# untitled.net
KiCad netlist of a schematic drawn in EAGLE
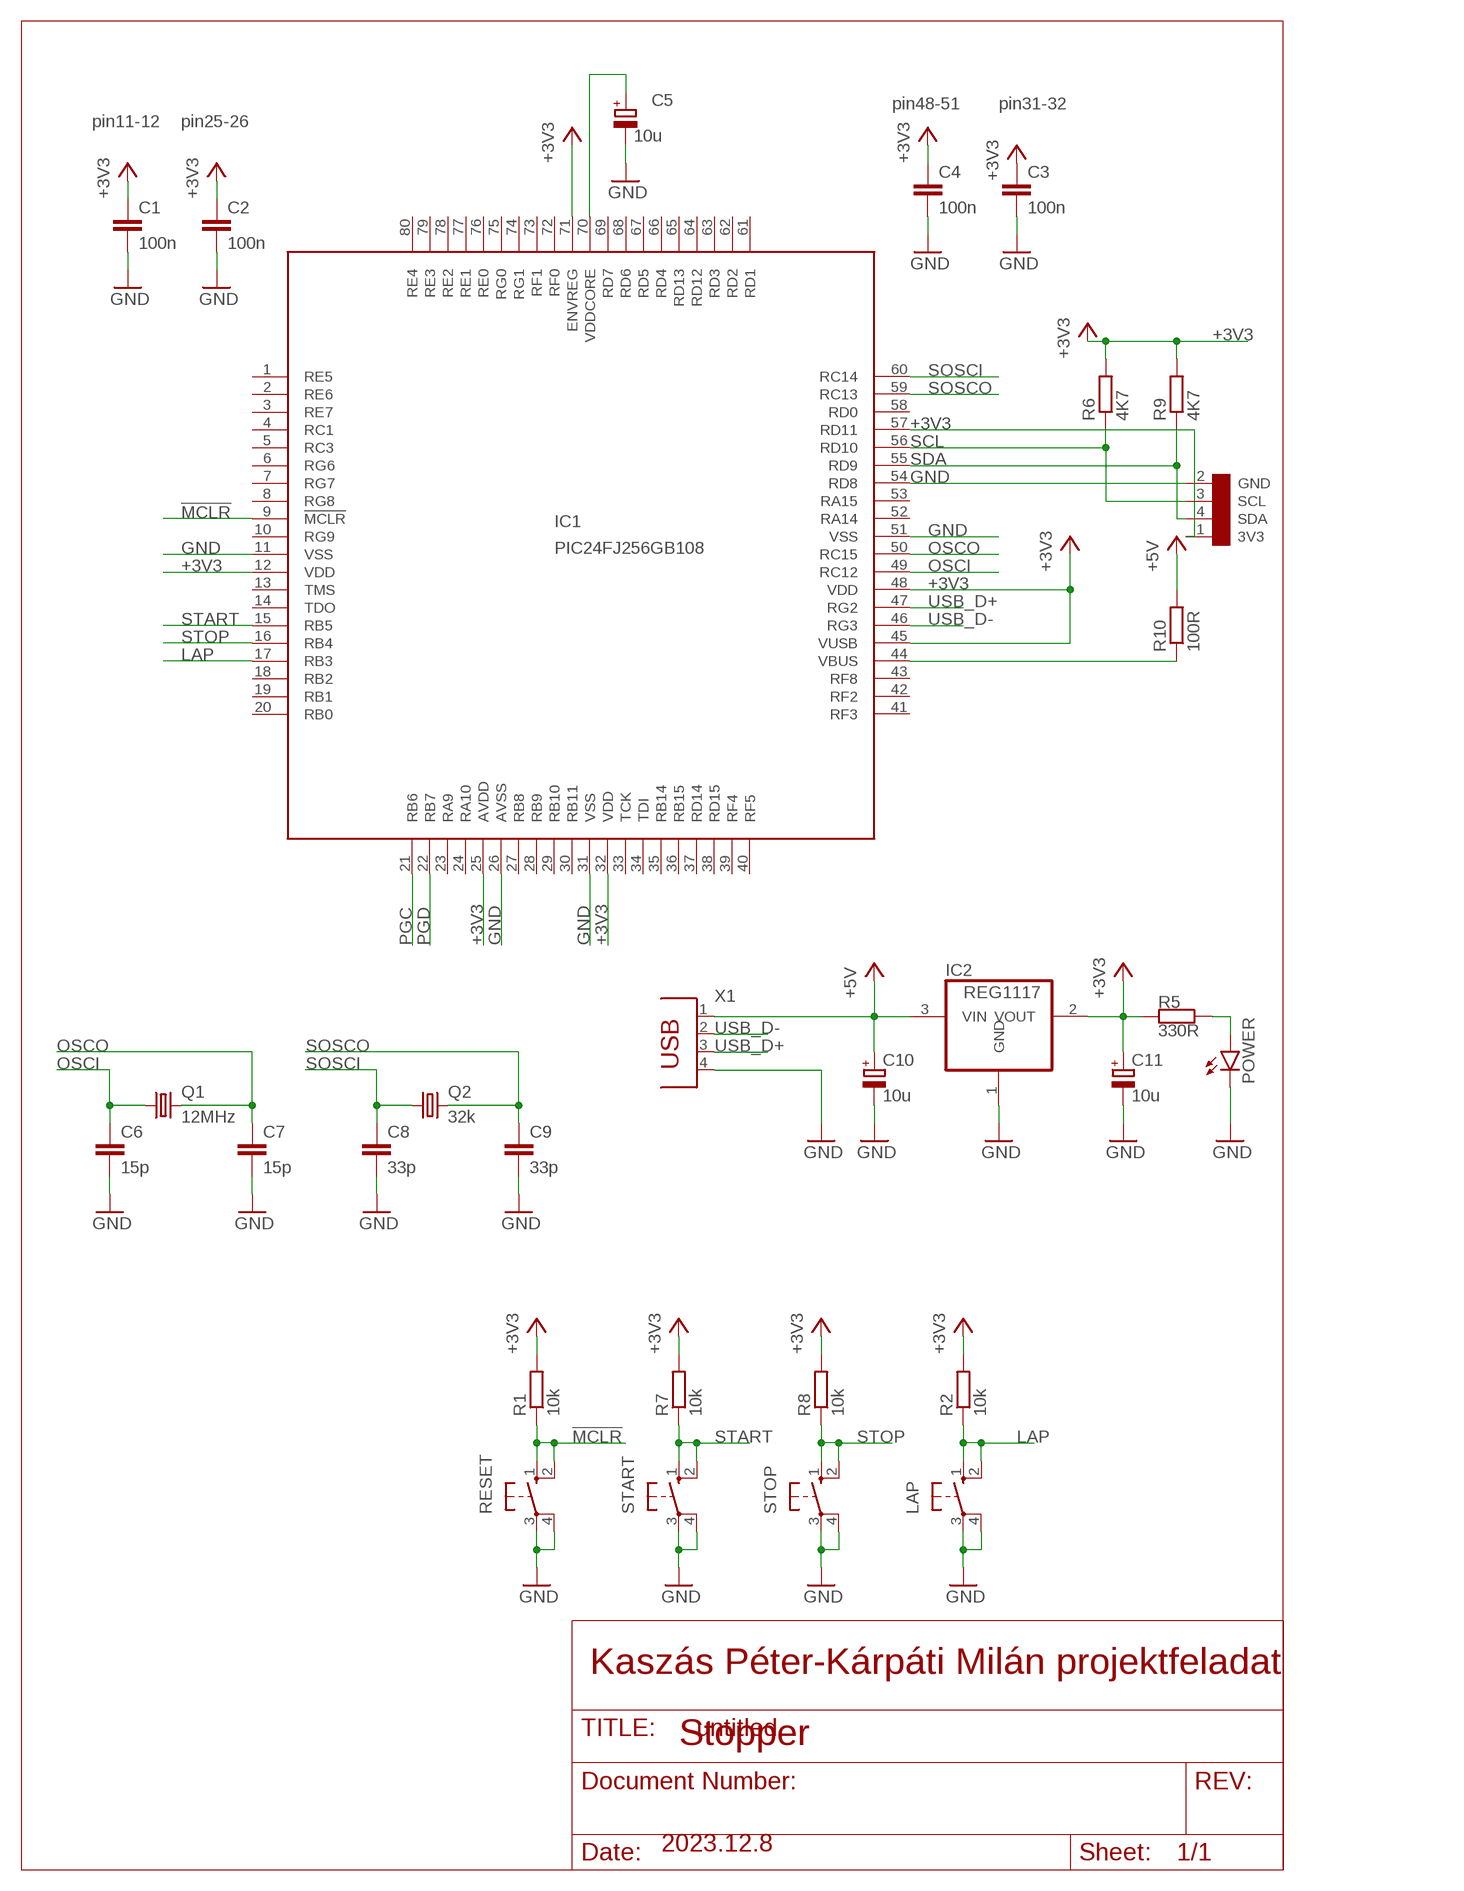
[diagram p0: schematic, sheet 1]

(export (version "E")
  (design (tool "Eeschema 10.0.6"))
  (components
    (comp (ref "C1")
      (value "100n")
      (footprint "eagle-import:C1206")
      (libsource (lib "eagle-import") (part "C-EUC1206"))
    )
    (comp (ref "C2")
      (value "100n")
      (footprint "eagle-import:C1206")
      (libsource (lib "eagle-import") (part "C-EUC1206"))
    )
    (comp (ref "C3")
      (value "100n")
      (footprint "eagle-import:C1206")
      (libsource (lib "eagle-import") (part "C-EUC1206"))
    )
    (comp (ref "C4")
      (value "100n")
      (footprint "eagle-import:C1206")
      (libsource (lib "eagle-import") (part "C-EUC1206"))
    )
    (comp (ref "C5")
      (value "10u")
      (footprint "eagle-import:SMC_D")
      (libsource (lib "eagle-import") (part "CPOL-EUSMCD"))
    )
    (comp (ref "C6")
      (value "15p")
      (footprint "eagle-import:C1206")
      (libsource (lib "eagle-import") (part "C-EUC1206"))
    )
    (comp (ref "C7")
      (value "15p")
      (footprint "eagle-import:C1206")
      (libsource (lib "eagle-import") (part "C-EUC1206"))
    )
    (comp (ref "C8")
      (value "33p")
      (footprint "eagle-import:C1206")
      (libsource (lib "eagle-import") (part "C-EUC1206"))
    )
    (comp (ref "C9")
      (value "33p")
      (footprint "eagle-import:C1206")
      (libsource (lib "eagle-import") (part "C-EUC1206"))
    )
    (comp (ref "C10")
      (value "10u")
      (footprint "eagle-import:SMC_D")
      (libsource (lib "eagle-import") (part "CPOL-EUSMCD"))
    )
    (comp (ref "C11")
      (value "10u")
      (footprint "eagle-import:SMC_D")
      (libsource (lib "eagle-import") (part "CPOL-EUSMCD"))
    )
    (comp (ref "CON1")
      (value "ICSPI2CTUSKE")
      (footprint "eagle-import:HDRV4W64P254_1X4_1016X508X838B")
      (libsource (lib "eagle-import") (part "ICSPI2CTUSKE"))
    )
    (comp (ref "IC1")
      (value "PIC24FJ256GB108")
      (footprint "eagle-import:TQFP80-12X12")
      (fields (field (name "MPN") "PIC24FJ256GB108-I/PT"))
      (libsource (lib "eagle-import") (part "PIC24FJ256GB108"))
    )
    (comp (ref "IC2")
      (value "REG1117")
      (footprint "eagle-import:SOT223")
      (libsource (lib "eagle-import") (part "REG1117"))
    )
    (comp (ref "LAP")
      (value "10-XX")
      (footprint "eagle-import:B3F-10XX")
      (fields (field (name "MPN") "B3F-1000"))
      (libsource (lib "eagle-import") (part "10-XX"))
    )
    (comp (ref "POWER")
      (value "LED5MM")
      (footprint "eagle-import:LED5MM")
      (libsource (lib "eagle-import") (part "LED5MM"))
    )
    (comp (ref "Q1")
      (value "12MHz")
      (footprint "eagle-import:HC49U70")
      (libsource (lib "eagle-import") (part "CRYSTALHC49U70"))
    )
    (comp (ref "Q2")
      (value "32k")
      (footprint "eagle-import:TC26H")
      (libsource (lib "eagle-import") (part "CRYSTALTC26H"))
    )
    (comp (ref "R1")
      (value "10k")
      (footprint "eagle-import:R1206")
      (libsource (lib "eagle-import") (part "R-EU_R1206"))
    )
    (comp (ref "R2")
      (value "10k")
      (footprint "eagle-import:R1206")
      (libsource (lib "eagle-import") (part "R-EU_R1206"))
    )
    (comp (ref "R5")
      (value "330R")
      (footprint "eagle-import:R1206")
      (libsource (lib "eagle-import") (part "R-EU_R1206"))
    )
    (comp (ref "R6")
      (value "4K7")
      (footprint "eagle-import:R1206")
      (libsource (lib "eagle-import") (part "R-EU_R1206"))
    )
    (comp (ref "R7")
      (value "10k")
      (footprint "eagle-import:R1206")
      (libsource (lib "eagle-import") (part "R-EU_R1206"))
    )
    (comp (ref "R8")
      (value "10k")
      (footprint "eagle-import:R1206")
      (libsource (lib "eagle-import") (part "R-EU_R1206"))
    )
    (comp (ref "R9")
      (value "4K7")
      (footprint "eagle-import:R1206")
      (libsource (lib "eagle-import") (part "R-EU_R1206"))
    )
    (comp (ref "R10")
      (value "100R")
      (footprint "eagle-import:R1206")
      (libsource (lib "eagle-import") (part "R-EU_R1206"))
    )
    (comp (ref "RESET")
      (value "10-XX")
      (footprint "eagle-import:B3F-10XX")
      (fields (field (name "MPN") "B3F-1000"))
      (libsource (lib "eagle-import") (part "10-XX"))
    )
    (comp (ref "START")
      (value "10-XX")
      (footprint "eagle-import:B3F-10XX")
      (fields (field (name "MPN") "B3F-1000"))
      (libsource (lib "eagle-import") (part "10-XX"))
    )
    (comp (ref "STOP")
      (value "10-XX")
      (footprint "eagle-import:B3F-10XX")
      (fields (field (name "MPN") "B3F-1000"))
      (libsource (lib "eagle-import") (part "10-XX"))
    )
    (comp (ref "X1")
      (value "PN61729")
      (footprint "eagle-import:PN61729")
      (libsource (lib "eagle-import") (part "PN61729"))
    )
  )
  (nets
    (net (code "1") (name "+3V3") (class "Default")
      (node (ref "C1") (pin "1") (pinfunction "1_1") (pintype "passive"))
      (node (ref "C11") (pin "+") (pinfunction "+_+") (pintype "passive"))
      (node (ref "C2") (pin "1") (pinfunction "1_1") (pintype "passive"))
      (node (ref "C3") (pin "1") (pinfunction "1_1") (pintype "passive"))
      (node (ref "C4") (pin "1") (pinfunction "1_1") (pintype "passive"))
      (node (ref "CON1") (pin "1") (pinfunction "3V3_1") (pintype "bidirectional"))
      (node (ref "IC1") (pin "12") (pinfunction "VDD_12") (pintype "power_in"))
      (node (ref "IC1") (pin "25") (pinfunction "AVDD_25") (pintype "power_in"))
      (node (ref "IC1") (pin "32") (pinfunction "VDD_32") (pintype "power_in"))
      (node (ref "IC1") (pin "45") (pinfunction "VUSB_45") (pintype "passive"))
      (node (ref "IC1") (pin "48") (pinfunction "VDD_48") (pintype "power_in"))
      (node (ref "IC1") (pin "57") (pinfunction "RD11_57") (pintype "bidirectional"))
      (node (ref "IC1") (pin "71") (pinfunction "ENVREG_71") (pintype "passive"))
      (node (ref "IC2") (pin "2") (pinfunction "VOUT_2") (pintype "output"))
      (node (ref "R1") (pin "2") (pinfunction "2_2") (pintype "passive"))
      (node (ref "R2") (pin "2") (pinfunction "2_2") (pintype "passive"))
      (node (ref "R5") (pin "2") (pinfunction "2_2") (pintype "passive"))
      (node (ref "R6") (pin "2") (pinfunction "2_2") (pintype "passive"))
      (node (ref "R7") (pin "2") (pinfunction "2_2") (pintype "passive"))
      (node (ref "R8") (pin "2") (pinfunction "2_2") (pintype "passive"))
      (node (ref "R9") (pin "2") (pinfunction "2_2") (pintype "passive"))
    )
    (net (code "2") (name "+5V") (class "Default")
      (node (ref "C10") (pin "+") (pinfunction "+_+") (pintype "passive"))
      (node (ref "IC2") (pin "3") (pinfunction "VIN_3") (pintype "input"))
      (node (ref "R10") (pin "2") (pinfunction "2_2") (pintype "passive"))
      (node (ref "X1") (pin "1") (pinfunction "1_1") (pintype "passive"))
    )
    (net (code "3") (name "/LAP") (class "Default")
      (node (ref "IC1") (pin "17") (pinfunction "RB3_17") (pintype "bidirectional"))
      (node (ref "LAP") (pin "1") (pinfunction "S_1") (pintype "passive"))
      (node (ref "LAP") (pin "2") (pinfunction "S1_2") (pintype "passive"))
      (node (ref "R2") (pin "1") (pinfunction "1_1") (pintype "passive"))
    )
    (net (code "4") (name "/OSCI") (class "Default")
      (node (ref "C6") (pin "1") (pinfunction "1_1") (pintype "passive"))
      (node (ref "IC1") (pin "49") (pinfunction "RC12_49") (pintype "bidirectional"))
      (node (ref "Q1") (pin "1") (pinfunction "1_1") (pintype "passive"))
    )
    (net (code "5") (name "/OSCO") (class "Default")
      (node (ref "C7") (pin "1") (pinfunction "1_1") (pintype "passive"))
      (node (ref "IC1") (pin "50") (pinfunction "RC15_50") (pintype "bidirectional"))
      (node (ref "Q1") (pin "2") (pinfunction "2_2") (pintype "passive"))
    )
    (net (code "6") (name "/PGC") (class "Default")
      (node (ref "IC1") (pin "21") (pinfunction "RB6_21") (pintype "bidirectional"))
    )
    (net (code "7") (name "/PGD") (class "Default")
      (node (ref "IC1") (pin "22") (pinfunction "RB7_22") (pintype "bidirectional"))
    )
    (net (code "8") (name "/SCL") (class "Default")
      (node (ref "CON1") (pin "3") (pinfunction "SCL_3") (pintype "bidirectional"))
      (node (ref "IC1") (pin "56") (pinfunction "RD10_56") (pintype "bidirectional"))
      (node (ref "R6") (pin "1") (pinfunction "1_1") (pintype "passive"))
    )
    (net (code "9") (name "/SDA") (class "Default")
      (node (ref "CON1") (pin "4") (pinfunction "SDA_4") (pintype "bidirectional"))
      (node (ref "IC1") (pin "55") (pinfunction "RD9_55") (pintype "bidirectional"))
      (node (ref "R9") (pin "1") (pinfunction "1_1") (pintype "passive"))
    )
    (net (code "10") (name "/SOSCI") (class "Default")
      (node (ref "C8") (pin "1") (pinfunction "1_1") (pintype "passive"))
      (node (ref "IC1") (pin "60") (pinfunction "RC14_60") (pintype "bidirectional"))
      (node (ref "Q2") (pin "1") (pinfunction "1_1") (pintype "passive"))
    )
    (net (code "11") (name "/SOSCO") (class "Default")
      (node (ref "C9") (pin "1") (pinfunction "1_1") (pintype "passive"))
      (node (ref "IC1") (pin "59") (pinfunction "RC13_59") (pintype "bidirectional"))
      (node (ref "Q2") (pin "2") (pinfunction "2_2") (pintype "passive"))
    )
    (net (code "12") (name "/START") (class "Default")
      (node (ref "IC1") (pin "15") (pinfunction "RB5_15") (pintype "bidirectional"))
      (node (ref "R7") (pin "1") (pinfunction "1_1") (pintype "passive"))
      (node (ref "START") (pin "1") (pinfunction "S_1") (pintype "passive"))
      (node (ref "START") (pin "2") (pinfunction "S1_2") (pintype "passive"))
    )
    (net (code "13") (name "/STOP") (class "Default")
      (node (ref "IC1") (pin "16") (pinfunction "RB4_16") (pintype "bidirectional"))
      (node (ref "R8") (pin "1") (pinfunction "1_1") (pintype "passive"))
      (node (ref "STOP") (pin "1") (pinfunction "S_1") (pintype "passive"))
      (node (ref "STOP") (pin "2") (pinfunction "S1_2") (pintype "passive"))
    )
    (net (code "14") (name "/USB_D+") (class "Default")
      (node (ref "IC1") (pin "47") (pinfunction "RG2_47") (pintype "bidirectional"))
      (node (ref "X1") (pin "3") (pinfunction "3_3") (pintype "passive"))
    )
    (net (code "15") (name "/USB_D-") (class "Default")
      (node (ref "IC1") (pin "46") (pinfunction "RG3_46") (pintype "bidirectional"))
      (node (ref "X1") (pin "2") (pinfunction "2_2") (pintype "passive"))
    )
    (net (code "16") (name "/~{MCLR}") (class "Default")
      (node (ref "IC1") (pin "9") (pinfunction "~{MCLR}_9") (pintype "bidirectional"))
      (node (ref "R1") (pin "1") (pinfunction "1_1") (pintype "passive"))
      (node (ref "RESET") (pin "1") (pinfunction "S_1") (pintype "passive"))
      (node (ref "RESET") (pin "2") (pinfunction "S1_2") (pintype "passive"))
    )
    (net (code "17") (name "GND") (class "Default")
      (node (ref "C1") (pin "2") (pinfunction "2_2") (pintype "passive"))
      (node (ref "C10") (pin "-") (pinfunction "-_-") (pintype "passive"))
      (node (ref "C11") (pin "-") (pinfunction "-_-") (pintype "passive"))
      (node (ref "C2") (pin "2") (pinfunction "2_2") (pintype "passive"))
      (node (ref "C3") (pin "2") (pinfunction "2_2") (pintype "passive"))
      (node (ref "C4") (pin "2") (pinfunction "2_2") (pintype "passive"))
      (node (ref "C5") (pin "-") (pinfunction "-_-") (pintype "passive"))
      (node (ref "C6") (pin "2") (pinfunction "2_2") (pintype "passive"))
      (node (ref "C7") (pin "2") (pinfunction "2_2") (pintype "passive"))
      (node (ref "C8") (pin "2") (pinfunction "2_2") (pintype "passive"))
      (node (ref "C9") (pin "2") (pinfunction "2_2") (pintype "passive"))
      (node (ref "CON1") (pin "2") (pinfunction "GND_2") (pintype "bidirectional"))
      (node (ref "IC1") (pin "11") (pinfunction "VSS_11") (pintype "power_in"))
      (node (ref "IC1") (pin "26") (pinfunction "AVSS_26") (pintype "power_in"))
      (node (ref "IC1") (pin "31") (pinfunction "VSS_31") (pintype "power_in"))
      (node (ref "IC1") (pin "51") (pinfunction "VSS_51") (pintype "power_in"))
      (node (ref "IC1") (pin "54") (pinfunction "RD8_54") (pintype "bidirectional"))
      (node (ref "IC2") (pin "1") (pinfunction "GND_1") (pintype "power_in"))
      (node (ref "LAP") (pin "3") (pinfunction "P_3") (pintype "passive"))
      (node (ref "LAP") (pin "4") (pinfunction "P1_4") (pintype "passive"))
      (node (ref "POWER") (pin "K") (pinfunction "C_K") (pintype "passive"))
      (node (ref "RESET") (pin "3") (pinfunction "P_3") (pintype "passive"))
      (node (ref "RESET") (pin "4") (pinfunction "P1_4") (pintype "passive"))
      (node (ref "START") (pin "3") (pinfunction "P_3") (pintype "passive"))
      (node (ref "START") (pin "4") (pinfunction "P1_4") (pintype "passive"))
      (node (ref "STOP") (pin "3") (pinfunction "P_3") (pintype "passive"))
      (node (ref "STOP") (pin "4") (pinfunction "P1_4") (pintype "passive"))
      (node (ref "X1") (pin "4") (pinfunction "4_4") (pintype "passive"))
    )
    (net (code "18") (name "Net-(IC1-VBUS)") (class "Default")
      (node (ref "IC1") (pin "44") (pinfunction "VBUS_44") (pintype "passive"))
      (node (ref "R10") (pin "1") (pinfunction "1_1") (pintype "passive"))
    )
    (net (code "19") (name "Net-(IC1-VDDCORE)") (class "Default")
      (node (ref "C5") (pin "+") (pinfunction "+_+") (pintype "passive"))
      (node (ref "IC1") (pin "70") (pinfunction "VDDCORE_70") (pintype "power_in"))
    )
    (net (code "20") (name "Net-(POWER-PadA)") (class "Default")
      (node (ref "POWER") (pin "A") (pinfunction "A_A") (pintype "passive"))
      (node (ref "R5") (pin "1") (pinfunction "1_1") (pintype "passive"))
    )
    (net (code "21") (name "unconnected-(IC1-RA9-Pad23)") (class "Default")
      (node (ref "IC1") (pin "23") (pinfunction "RA9_23") (pintype "bidirectional"))
    )
    (net (code "22") (name "unconnected-(IC1-RA10-Pad24)") (class "Default")
      (node (ref "IC1") (pin "24") (pinfunction "RA10_24") (pintype "bidirectional"))
    )
    (net (code "23") (name "unconnected-(IC1-RA14-Pad52)") (class "Default")
      (node (ref "IC1") (pin "52") (pinfunction "RA14_52") (pintype "bidirectional"))
    )
    (net (code "24") (name "unconnected-(IC1-RA15-Pad53)") (class "Default")
      (node (ref "IC1") (pin "53") (pinfunction "RA15_53") (pintype "bidirectional"))
    )
    (net (code "25") (name "unconnected-(IC1-RB0-Pad20)") (class "Default")
      (node (ref "IC1") (pin "20") (pinfunction "RB0_20") (pintype "bidirectional"))
    )
    (net (code "26") (name "unconnected-(IC1-RB1-Pad19)") (class "Default")
      (node (ref "IC1") (pin "19") (pinfunction "RB1_19") (pintype "bidirectional"))
    )
    (net (code "27") (name "unconnected-(IC1-RB2-Pad18)") (class "Default")
      (node (ref "IC1") (pin "18") (pinfunction "RB2_18") (pintype "bidirectional"))
    )
    (net (code "28") (name "unconnected-(IC1-RB8-Pad27)") (class "Default")
      (node (ref "IC1") (pin "27") (pinfunction "RB8_27") (pintype "bidirectional"))
    )
    (net (code "29") (name "unconnected-(IC1-RB9-Pad28)") (class "Default")
      (node (ref "IC1") (pin "28") (pinfunction "RB9_28") (pintype "bidirectional"))
    )
    (net (code "30") (name "unconnected-(IC1-RB10-Pad29)") (class "Default")
      (node (ref "IC1") (pin "29") (pinfunction "RB10_29") (pintype "bidirectional"))
    )
    (net (code "31") (name "unconnected-(IC1-RB11-Pad30)") (class "Default")
      (node (ref "IC1") (pin "30") (pinfunction "RB11_30") (pintype "bidirectional"))
    )
    (net (code "32") (name "unconnected-(IC1-RB14-Pad35)") (class "Default")
      (node (ref "IC1") (pin "35") (pinfunction "RB14_35") (pintype "bidirectional"))
    )
    (net (code "33") (name "unconnected-(IC1-RB15-Pad36)") (class "Default")
      (node (ref "IC1") (pin "36") (pinfunction "RB15_36") (pintype "bidirectional"))
    )
    (net (code "34") (name "unconnected-(IC1-RC1-Pad4)") (class "Default")
      (node (ref "IC1") (pin "4") (pinfunction "RC1_4") (pintype "bidirectional"))
    )
    (net (code "35") (name "unconnected-(IC1-RC3-Pad5)") (class "Default")
      (node (ref "IC1") (pin "5") (pinfunction "RC3_5") (pintype "bidirectional"))
    )
    (net (code "36") (name "unconnected-(IC1-RD0-Pad58)") (class "Default")
      (node (ref "IC1") (pin "58") (pinfunction "RD0_58") (pintype "bidirectional"))
    )
    (net (code "37") (name "unconnected-(IC1-RD1-Pad61)") (class "Default")
      (node (ref "IC1") (pin "61") (pinfunction "RD1_61") (pintype "bidirectional"))
    )
    (net (code "38") (name "unconnected-(IC1-RD2-Pad62)") (class "Default")
      (node (ref "IC1") (pin "62") (pinfunction "RD2_62") (pintype "bidirectional"))
    )
    (net (code "39") (name "unconnected-(IC1-RD3-Pad63)") (class "Default")
      (node (ref "IC1") (pin "63") (pinfunction "RD3_63") (pintype "bidirectional"))
    )
    (net (code "40") (name "unconnected-(IC1-RD4-Pad66)") (class "Default")
      (node (ref "IC1") (pin "66") (pinfunction "RD4_66") (pintype "bidirectional"))
    )
    (net (code "41") (name "unconnected-(IC1-RD5-Pad67)") (class "Default")
      (node (ref "IC1") (pin "67") (pinfunction "RD5_67") (pintype "bidirectional"))
    )
    (net (code "42") (name "unconnected-(IC1-RD6-Pad68)") (class "Default")
      (node (ref "IC1") (pin "68") (pinfunction "RD6_68") (pintype "bidirectional"))
    )
    (net (code "43") (name "unconnected-(IC1-RD7-Pad69)") (class "Default")
      (node (ref "IC1") (pin "69") (pinfunction "RD7_69") (pintype "bidirectional"))
    )
    (net (code "44") (name "unconnected-(IC1-RD12-Pad64)") (class "Default")
      (node (ref "IC1") (pin "64") (pinfunction "RD12_64") (pintype "bidirectional"))
    )
    (net (code "45") (name "unconnected-(IC1-RD13-Pad65)") (class "Default")
      (node (ref "IC1") (pin "65") (pinfunction "RD13_65") (pintype "bidirectional"))
    )
    (net (code "46") (name "unconnected-(IC1-RD14-Pad37)") (class "Default")
      (node (ref "IC1") (pin "37") (pinfunction "RD14_37") (pintype "bidirectional"))
    )
    (net (code "47") (name "unconnected-(IC1-RD15-Pad38)") (class "Default")
      (node (ref "IC1") (pin "38") (pinfunction "RD15_38") (pintype "bidirectional"))
    )
    (net (code "48") (name "unconnected-(IC1-RE0-Pad76)") (class "Default")
      (node (ref "IC1") (pin "76") (pinfunction "RE0_76") (pintype "bidirectional"))
    )
    (net (code "49") (name "unconnected-(IC1-RE1-Pad77)") (class "Default")
      (node (ref "IC1") (pin "77") (pinfunction "RE1_77") (pintype "bidirectional"))
    )
    (net (code "50") (name "unconnected-(IC1-RE2-Pad78)") (class "Default")
      (node (ref "IC1") (pin "78") (pinfunction "RE2_78") (pintype "bidirectional"))
    )
    (net (code "51") (name "unconnected-(IC1-RE3-Pad79)") (class "Default")
      (node (ref "IC1") (pin "79") (pinfunction "RE3_79") (pintype "bidirectional"))
    )
    (net (code "52") (name "unconnected-(IC1-RE4-Pad80)") (class "Default")
      (node (ref "IC1") (pin "80") (pinfunction "RE4_80") (pintype "bidirectional"))
    )
    (net (code "53") (name "unconnected-(IC1-RE5-Pad1)") (class "Default")
      (node (ref "IC1") (pin "1") (pinfunction "RE5_1") (pintype "bidirectional"))
    )
    (net (code "54") (name "unconnected-(IC1-RE6-Pad2)") (class "Default")
      (node (ref "IC1") (pin "2") (pinfunction "RE6_2") (pintype "bidirectional"))
    )
    (net (code "55") (name "unconnected-(IC1-RE7-Pad3)") (class "Default")
      (node (ref "IC1") (pin "3") (pinfunction "RE7_3") (pintype "bidirectional"))
    )
    (net (code "56") (name "unconnected-(IC1-RF0-Pad72)") (class "Default")
      (node (ref "IC1") (pin "72") (pinfunction "RF0_72") (pintype "bidirectional"))
    )
    (net (code "57") (name "unconnected-(IC1-RF1-Pad73)") (class "Default")
      (node (ref "IC1") (pin "73") (pinfunction "RF1_73") (pintype "bidirectional"))
    )
    (net (code "58") (name "unconnected-(IC1-RF2-Pad42)") (class "Default")
      (node (ref "IC1") (pin "42") (pinfunction "RF2_42") (pintype "bidirectional"))
    )
    (net (code "59") (name "unconnected-(IC1-RF3-Pad41)") (class "Default")
      (node (ref "IC1") (pin "41") (pinfunction "RF3_41") (pintype "bidirectional"))
    )
    (net (code "60") (name "unconnected-(IC1-RF4-Pad39)") (class "Default")
      (node (ref "IC1") (pin "39") (pinfunction "RF4_39") (pintype "bidirectional"))
    )
    (net (code "61") (name "unconnected-(IC1-RF5-Pad40)") (class "Default")
      (node (ref "IC1") (pin "40") (pinfunction "RF5_40") (pintype "bidirectional"))
    )
    (net (code "62") (name "unconnected-(IC1-RF8-Pad43)") (class "Default")
      (node (ref "IC1") (pin "43") (pinfunction "RF8_43") (pintype "bidirectional"))
    )
    (net (code "63") (name "unconnected-(IC1-RG0-Pad75)") (class "Default")
      (node (ref "IC1") (pin "75") (pinfunction "RG0_75") (pintype "bidirectional"))
    )
    (net (code "64") (name "unconnected-(IC1-RG1-Pad74)") (class "Default")
      (node (ref "IC1") (pin "74") (pinfunction "RG1_74") (pintype "bidirectional"))
    )
    (net (code "65") (name "unconnected-(IC1-RG6-Pad6)") (class "Default")
      (node (ref "IC1") (pin "6") (pinfunction "RG6_6") (pintype "bidirectional"))
    )
    (net (code "66") (name "unconnected-(IC1-RG7-Pad7)") (class "Default")
      (node (ref "IC1") (pin "7") (pinfunction "RG7_7") (pintype "bidirectional"))
    )
    (net (code "67") (name "unconnected-(IC1-RG8-Pad8)") (class "Default")
      (node (ref "IC1") (pin "8") (pinfunction "RG8_8") (pintype "bidirectional"))
    )
    (net (code "68") (name "unconnected-(IC1-RG9-Pad10)") (class "Default")
      (node (ref "IC1") (pin "10") (pinfunction "RG9_10") (pintype "bidirectional"))
    )
    (net (code "69") (name "unconnected-(IC1-TCK-Pad33)") (class "Default")
      (node (ref "IC1") (pin "33") (pinfunction "TCK_33") (pintype "input"))
    )
    (net (code "70") (name "unconnected-(IC1-TDI-Pad34)") (class "Default")
      (node (ref "IC1") (pin "34") (pinfunction "TDI_34") (pintype "input"))
    )
    (net (code "71") (name "unconnected-(IC1-TDO-Pad14)") (class "Default")
      (node (ref "IC1") (pin "14") (pinfunction "TDO_14") (pintype "output"))
    )
    (net (code "72") (name "unconnected-(IC1-TMS-Pad13)") (class "Default")
      (node (ref "IC1") (pin "13") (pinfunction "TMS_13") (pintype "input"))
    )
  )
)
